# 01-MCU-V2_1.net
KiCad netlist of a schematic drawn in Altium Designer
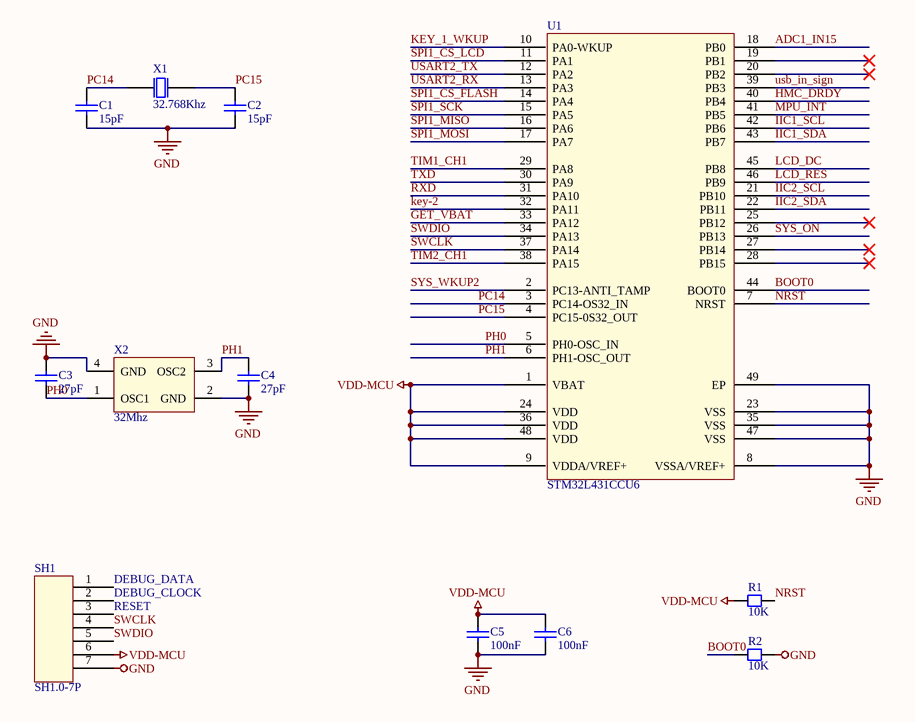
[diagram p0: 01-MCU-V2.1.SchDoc]

(export (version "E")
  (design (tool "Eeschema 10.0.6"))
  (components
    (comp (ref "C1")
      (value "15pF")
      (footprint "CC1005-0402")
      (description "贴片电容")
      (libsource (lib "tianxiaohua_Schlib") (part "Chip capacitor"))
    )
    (comp (ref "C2")
      (value "15pF")
      (footprint "CC1005-0402")
      (description "贴片电容")
      (libsource (lib "tianxiaohua_Schlib") (part "Chip capacitor"))
    )
    (comp (ref "C3")
      (value "27pF")
      (footprint "CC1005-0402")
      (description "贴片电容")
      (libsource (lib "tianxiaohua_Schlib") (part "Chip capacitor"))
    )
    (comp (ref "C4")
      (value "27pF")
      (footprint "CC1005-0402")
      (description "贴片电容")
      (libsource (lib "tianxiaohua_Schlib") (part "Chip capacitor"))
    )
    (comp (ref "C5")
      (value "100nF")
      (footprint "CC1005-0402")
      (description "贴片电容")
      (libsource (lib "tianxiaohua_Schlib") (part "Chip capacitor"))
    )
    (comp (ref "C6")
      (value "100nF")
      (footprint "CC1005-0402")
      (description "贴片电容")
      (libsource (lib "tianxiaohua_Schlib") (part "Chip capacitor"))
    )
    (comp (ref "R1")
      (value "10K")
      (footprint "CR1005-0402")
      (description "贴片电阻")
      (libsource (lib "tianxiaohua_Schlib") (part "Chip resistor"))
    )
    (comp (ref "R2")
      (value "10K")
      (footprint "CR1005-0402")
      (description "贴片电阻")
      (libsource (lib "tianxiaohua_Schlib") (part "Chip resistor"))
    )
    (comp (ref "SH1")
      (value "SH1.0-7P")
      (footprint "SH1.0-6P")
      (description "间距为1mm的端子")
      (libsource (lib "tianxiaohua_Schlib") (part "SH1.0-7P"))
    )
    (comp (ref "U1")
      (value "STM32L431CCU6")
      (footprint "STM32-UFQFPN48_N")
      (description "stm32低功耗单片机 主频80MHz")
      (libsource (lib "tianxiaohua_Schlib") (part "STM32L431CCU6"))
    )
    (comp (ref "X1")
      (value "32.768Khz")
      (footprint "XTAL-2012")
      (description "2012封装的时钟晶振")
      (libsource (lib "tianxiaohua_Schlib") (part "XTAL 2012"))
    )
    (comp (ref "X2")
      (value "32Mhz")
      (footprint "XTAL-2016")
      (description "2016封装的晶振")
      (libsource (lib "tianxiaohua_Schlib") (part "XTAL 2016"))
    )
  )
  (nets
    (net (code "1") (name "/ADC1_IN15") (class "Default")
      (node (ref "U1") (pin "18") (pinfunction "PB0_18") (pintype "passive"))
    )
    (net (code "2") (name "/BOOT0") (class "Default")
      (node (ref "R2") (pin "2") (pinfunction "2_2") (pintype "passive"))
      (node (ref "U1") (pin "44") (pinfunction "BOOT0_44") (pintype "passive"))
    )
    (net (code "3") (name "/DEBUG_CLOCK") (class "Default")
      (node (ref "SH1") (pin "2") (pinfunction "2_2") (pintype "passive"))
    )
    (net (code "4") (name "/DEBUG_DATA") (class "Default") (node (ref "SH1") (pin "1") (pintype "passive")))
    (net (code "5") (name "/GET_VBAT") (class "Default")
      (node (ref "U1") (pin "33") (pinfunction "PA12_33") (pintype "passive"))
    )
    (net (code "6") (name "/HMC_DRDY") (class "Default")
      (node (ref "U1") (pin "40") (pinfunction "PB4_40") (pintype "passive"))
    )
    (net (code "7") (name "/IIC1_SCL") (class "Default")
      (node (ref "U1") (pin "42") (pinfunction "PB6_42") (pintype "passive"))
    )
    (net (code "8") (name "/IIC1_SDA") (class "Default")
      (node (ref "U1") (pin "43") (pinfunction "PB7_43") (pintype "passive"))
    )
    (net (code "9") (name "/IIC2_SCL") (class "Default")
      (node (ref "U1") (pin "21") (pinfunction "PB10_21") (pintype "passive"))
    )
    (net (code "10") (name "/IIC2_SDA") (class "Default")
      (node (ref "U1") (pin "22") (pinfunction "PB11_22") (pintype "passive"))
    )
    (net (code "11") (name "/KEY_1_WKUP") (class "Default")
      (node (ref "U1") (pin "10") (pinfunction "PA0-WKUP_10") (pintype "passive"))
    )
    (net (code "12") (name "/LCD_DC") (class "Default")
      (node (ref "U1") (pin "45") (pinfunction "PB8_45") (pintype "passive"))
    )
    (net (code "13") (name "/LCD_RES") (class "Default")
      (node (ref "U1") (pin "46") (pinfunction "PB9_46") (pintype "passive"))
    )
    (net (code "14") (name "/MPU_INT") (class "Default")
      (node (ref "U1") (pin "41") (pinfunction "PB5_41") (pintype "passive"))
    )
    (net (code "15") (name "/NRST") (class "Default")
      (node (ref "R1") (pin "1") (pinfunction "1_1") (pintype "passive"))
      (node (ref "U1") (pin "7") (pinfunction "NRST_7") (pintype "passive"))
    )
    (net (code "16") (name "/PC14") (class "Default")
      (node (ref "C1") (pin "2") (pinfunction "2_2") (pintype "passive"))
      (node (ref "U1") (pin "3") (pinfunction "PC14-OS32_IN_3") (pintype "passive"))
      (node (ref "X1") (pin "2") (pinfunction "2_2") (pintype "passive"))
    )
    (net (code "17") (name "/PC15") (class "Default")
      (node (ref "C2") (pin "2") (pinfunction "2_2") (pintype "passive"))
      (node (ref "U1") (pin "4") (pinfunction "PC15-0S32_OUT_4") (pintype "passive"))
      (node (ref "X1") (pin "1") (pinfunction "1_1") (pintype "passive"))
    )
    (net (code "18") (name "/PH0") (class "Default")
      (node (ref "C3") (pin "1") (pinfunction "1_1") (pintype "passive"))
      (node (ref "U1") (pin "5") (pinfunction "PH0-OSC_IN_5") (pintype "passive"))
      (node (ref "X2") (pin "1") (pinfunction "OSC1_1") (pintype "passive"))
    )
    (net (code "19") (name "/PH1") (class "Default")
      (node (ref "C4") (pin "2") (pinfunction "2_2") (pintype "passive"))
      (node (ref "U1") (pin "6") (pinfunction "PH1-OSC_OUT_6") (pintype "passive"))
      (node (ref "X2") (pin "3") (pinfunction "OSC2_3") (pintype "passive"))
    )
    (net (code "20") (name "/RESET") (class "Default") (node (ref "SH1") (pin "3") (pintype "passive")))
    (net (code "21") (name "/RXD") (class "Default")
      (node (ref "U1") (pin "31") (pinfunction "PA10_31") (pintype "passive"))
    )
    (net (code "22") (name "/SPI1_CS_FLASH") (class "Default")
      (node (ref "U1") (pin "14") (pinfunction "PA4_14") (pintype "passive"))
    )
    (net (code "23") (name "/SPI1_CS_LCD") (class "Default")
      (node (ref "U1") (pin "11") (pinfunction "PA1_11") (pintype "passive"))
    )
    (net (code "24") (name "/SPI1_MISO") (class "Default")
      (node (ref "U1") (pin "16") (pinfunction "PA6_16") (pintype "passive"))
    )
    (net (code "25") (name "/SPI1_MOSI") (class "Default")
      (node (ref "U1") (pin "17") (pinfunction "PA7_17") (pintype "passive"))
    )
    (net (code "26") (name "/SPI1_SCK") (class "Default")
      (node (ref "U1") (pin "15") (pinfunction "PA5_15") (pintype "passive"))
    )
    (net (code "27") (name "/SWCLK") (class "Default")
      (node (ref "SH1") (pin "4") (pinfunction "4_4") (pintype "passive"))
      (node (ref "U1") (pin "37") (pinfunction "PA14_37") (pintype "passive"))
    )
    (net (code "28") (name "/SWDIO") (class "Default")
      (node (ref "SH1") (pin "5") (pintype "passive"))
      (node (ref "U1") (pin "34") (pinfunction "PA13_34") (pintype "passive"))
    )
    (net (code "29") (name "/SYS_ON") (class "Default")
      (node (ref "U1") (pin "26") (pinfunction "PB13_26") (pintype "passive"))
    )
    (net (code "30") (name "/SYS_WKUP2") (class "Default")
      (node (ref "U1") (pin "2") (pinfunction "PC13-ANTI_TAMP_2") (pintype "passive"))
    )
    (net (code "31") (name "/TIM1_CH1") (class "Default")
      (node (ref "U1") (pin "29") (pinfunction "PA8_29") (pintype "passive"))
    )
    (net (code "32") (name "/TIM2_CH1") (class "Default")
      (node (ref "U1") (pin "38") (pinfunction "PA15_38") (pintype "passive"))
    )
    (net (code "33") (name "/TXD") (class "Default")
      (node (ref "U1") (pin "30") (pinfunction "PA9_30") (pintype "passive"))
    )
    (net (code "34") (name "/USART2_RX") (class "Default")
      (node (ref "U1") (pin "13") (pinfunction "PA3_13") (pintype "passive"))
    )
    (net (code "35") (name "/USART2_TX") (class "Default")
      (node (ref "U1") (pin "12") (pinfunction "PA2_12") (pintype "passive"))
    )
    (net (code "36") (name "/key-2") (class "Default")
      (node (ref "U1") (pin "32") (pinfunction "PA11_32") (pintype "passive"))
    )
    (net (code "37") (name "/usb_in_sign") (class "Default")
      (node (ref "U1") (pin "39") (pinfunction "PB3_39") (pintype "passive"))
    )
    (net (code "38") (name "GND") (class "Default")
      (node (ref "C1") (pin "1") (pinfunction "1_1") (pintype "passive"))
      (node (ref "C2") (pin "1") (pinfunction "1_1") (pintype "passive"))
      (node (ref "C3") (pin "2") (pinfunction "2_2") (pintype "passive"))
      (node (ref "C4") (pin "1") (pinfunction "1_1") (pintype "passive"))
      (node (ref "C5") (pin "1") (pinfunction "1_1") (pintype "passive"))
      (node (ref "C6") (pin "1") (pinfunction "1_1") (pintype "passive"))
      (node (ref "R2") (pin "1") (pinfunction "1_1") (pintype "passive"))
      (node (ref "SH1") (pin "7") (pinfunction "7_7") (pintype "passive"))
      (node (ref "U1") (pin "23") (pinfunction "VSS_23") (pintype "passive"))
      (node (ref "U1") (pin "35") (pinfunction "VSS_35") (pintype "passive"))
      (node (ref "U1") (pin "47") (pinfunction "VSS_47") (pintype "passive"))
      (node (ref "U1") (pin "49") (pinfunction "EP_49") (pintype "passive"))
      (node (ref "U1") (pin "8") (pinfunction "VSSA/VREF+_8") (pintype "passive"))
      (node (ref "X2") (pin "2") (pinfunction "GND_2") (pintype "passive"))
      (node (ref "X2") (pin "4") (pinfunction "GND_4") (pintype "passive"))
    )
    (net (code "39") (name "VDD-MCU") (class "Default")
      (node (ref "C5") (pin "2") (pinfunction "2_2") (pintype "passive"))
      (node (ref "C6") (pin "2") (pinfunction "2_2") (pintype "passive"))
      (node (ref "R1") (pin "2") (pinfunction "2_2") (pintype "passive"))
      (node (ref "SH1") (pin "6") (pinfunction "6_6") (pintype "passive"))
      (node (ref "U1") (pin "1") (pinfunction "VBAT_1") (pintype "passive"))
      (node (ref "U1") (pin "24") (pinfunction "VDD_24") (pintype "passive"))
      (node (ref "U1") (pin "36") (pinfunction "VDD_36") (pintype "passive"))
      (node (ref "U1") (pin "48") (pinfunction "VDD_48") (pintype "passive"))
      (node (ref "U1") (pin "9") (pinfunction "VDDA/VREF+_9") (pintype "passive"))
    )
    (net (code "40") (name "unconnected-(U1-PB1-Pad19)") (class "Default")
      (node (ref "U1") (pin "19") (pinfunction "PB1_19") (pintype "passive+no_connect"))
    )
    (net (code "41") (name "unconnected-(U1-PB2-Pad20)") (class "Default")
      (node (ref "U1") (pin "20") (pinfunction "PB2_20") (pintype "passive+no_connect"))
    )
    (net (code "42") (name "unconnected-(U1-PB12-Pad25)") (class "Default")
      (node (ref "U1") (pin "25") (pinfunction "PB12_25") (pintype "passive+no_connect"))
    )
    (net (code "43") (name "unconnected-(U1-PB14-Pad27)") (class "Default")
      (node (ref "U1") (pin "27") (pinfunction "PB14_27") (pintype "passive+no_connect"))
    )
    (net (code "44") (name "unconnected-(U1-PB15-Pad28)") (class "Default")
      (node (ref "U1") (pin "28") (pinfunction "PB15_28") (pintype "passive+no_connect"))
    )
  )
)
